# Sheet1.net
KiCad netlist of a schematic drawn in Altium Designer
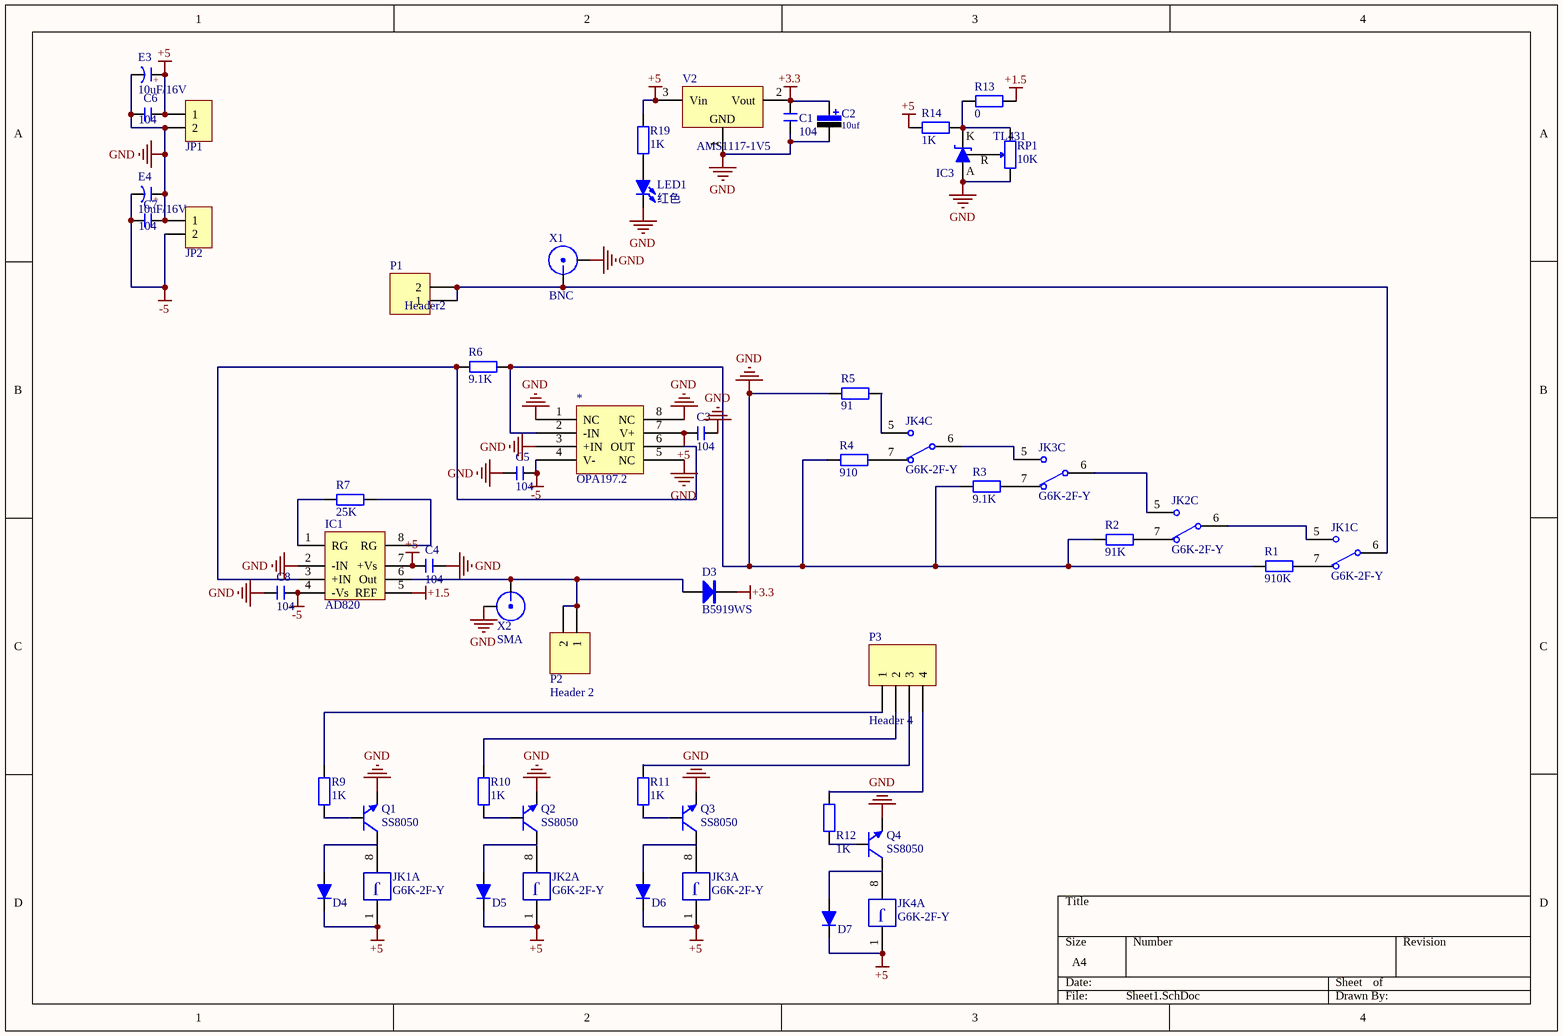
[diagram p0: Sheet1.SchDoc]

(export (version "E")
  (design (tool "Eeschema 10.0.6"))
  (components
    (comp (ref "*") (value "OPA197.2") (footprint "SOP-8") (libsource (lib "CommonUsed") (part "OPA197.2")))
    (comp (ref "C1")
      (value "104")
      (footprint "C 0603_L")
      (description "无极性贴片电容")
      (fields (field (name "版权归属") "源创客"))
      (libsource (lib "Library1") (part "C"))
    )
    (comp (ref "C2")
      (value "10uf")
      (footprint "C-DIP-5")
      (description "极性直插电解电容")
      (fields (field (name "Comment") "C"))
      (libsource (lib "Library") (part "Cap-Pol-ER"))
    )
    (comp (ref "C3")
      (value "104")
      (footprint "C 0603_L")
      (description "无极性贴片电容")
      (fields (field (name "版权归属") "源创客"))
      (libsource (lib "Library1") (part "C"))
    )
    (comp (ref "C4")
      (value "104")
      (footprint "C 0603_L")
      (description "无极性贴片电容")
      (fields (field (name "版权归属") "源创客"))
      (libsource (lib "Library1") (part "C"))
    )
    (comp (ref "C5")
      (value "104")
      (footprint "C 0603_L")
      (description "无极性贴片电容")
      (fields (field (name "版权归属") "源创客"))
      (libsource (lib "Library1") (part "C"))
    )
    (comp (ref "C6")
      (value "104")
      (footprint "C 0603_L")
      (description "无极性贴片电容")
      (fields (field (name "版权归属") "源创客"))
      (libsource (lib "Library1") (part "C"))
    )
    (comp (ref "C7")
      (value "104")
      (footprint "C 0603_L")
      (description "无极性贴片电容")
      (fields (field (name "版权归属") "源创客"))
      (libsource (lib "Library1") (part "C"))
    )
    (comp (ref "C8")
      (value "104")
      (footprint "C 0603_L")
      (description "无极性贴片电容")
      (fields (field (name "版权归属") "源创客"))
      (libsource (lib "Library1") (part "C"))
    )
    (comp (ref "D3")
      (value "B5919WS")
      (footprint "SMA")
      (description "肖特基二极管")
      (fields (field (name "版权归属") "源创客"))
      (libsource (lib "Library1") (part "1N5819"))
    )
    (comp (ref "D4")
      (value "D")
      (footprint "D-SMA")
      (description "二极管")
      (libsource (lib "Library") (part "Diode"))
    )
    (comp (ref "D5")
      (value "D")
      (footprint "D-SMA")
      (description "二极管")
      (libsource (lib "Library") (part "Diode"))
    )
    (comp (ref "D6")
      (value "D")
      (footprint "D-SMA")
      (description "二极管")
      (libsource (lib "Library") (part "Diode"))
    )
    (comp (ref "D7")
      (value "D")
      (footprint "D-SMA")
      (description "二极管")
      (libsource (lib "Library") (part "Diode"))
    )
    (comp (ref "E3")
      (value "10uF/16V")
      (footprint "CAP 2.5*5*11 - GD")
      (description "直插电解电容")
      (fields (field (name "版权归属") "源创客"))
      (libsource (lib "Library1") (part "C-CAP"))
    )
    (comp (ref "E4")
      (value "10uF/16V")
      (footprint "CAP 2.0*5*11")
      (description "直插电解电容")
      (fields (field (name "版权归属") "源创客"))
      (libsource (lib "Library1") (part "C-CAP"))
    )
    (comp (ref "IC1")
      (value "AD820")
      (footprint "SOP8_N")
      (description "仪表放大器")
      (libsource (lib "Library1") (part "AD620"))
    )
    (comp (ref "IC3")
      (value "TL431")
      (footprint "SOT23-3L")
      (description "可调基准稳压芯片")
      (fields (field (name "版权归属") "源创客"))
      (libsource (lib "Library1") (part "TL431_SMD"))
    )
    (comp (ref "JK1")
      (value "G6K-2F-Y")
      (footprint "G6K-2F-Y")
      (description "两组转换-信号型")
      (fields (field (name "版权归属") "源创客"))
      (libsource (lib "") (part "G6K-2F-Y_1"))
    )
    (comp (ref "JK2")
      (value "G6K-2F-Y")
      (footprint "G6K-2F-Y")
      (description "两组转换-信号型")
      (fields (field (name "版权归属") "源创客"))
      (libsource (lib "") (part "G6K-2F-Y_1"))
    )
    (comp (ref "JK3")
      (value "G6K-2F-Y")
      (footprint "G6K-2F-Y")
      (description "两组转换-信号型")
      (fields (field (name "版权归属") "源创客"))
      (libsource (lib "Library1") (part "G6K-2F-Y"))
    )
    (comp (ref "JK4")
      (value "G6K-2F-Y")
      (footprint "G6K-2F-Y")
      (description "两组转换-信号型")
      (fields (field (name "版权归属") "源创客"))
      (libsource (lib "") (part "G6K-2F-Y_1"))
    )
    (comp (ref "JP1")
      (value "HDR-1X2")
      (footprint "VH3.96-LI-2P")
      (description "2P接插件")
      (fields (field (name "版权归属") "源创客"))
      (libsource (lib "Library1") (part "Header 2"))
    )
    (comp (ref "JP2")
      (value "HDR-1X2")
      (footprint "VH3.96-LI-2P")
      (description "2P接插件")
      (fields (field (name "版权归属") "源创客"))
      (libsource (lib "Library1") (part "Header 2"))
    )
    (comp (ref "LED1")
      (value "红色")
      (footprint "LED 0805B")
      (description "贴片LED")
      (fields (field (name "版权归属") "源创客"))
      (libsource (lib "Library1") (part "LED-SMD"))
    )
    (comp (ref "P1")
      (value "Header2")
      (footprint "HDR1X2")
      (description "Header, 2-Pin")
      (fields (field (name "PUBLISHER") "Altium Limited"))
      (libsource (lib "") (part "Header 2_1"))
    )
    (comp (ref "P2")
      (value "Header 2")
      (footprint "HDR1X2")
      (description "Header, 2-Pin")
      (fields (field (name "PUBLISHER") "Altium Limited"))
      (libsource (lib "Miscellaneous Connectors") (part "Header 2"))
    )
    (comp (ref "P3")
      (value "Header 4")
      (footprint "HDR1X4")
      (description "Header, 4-Pin")
      (fields (field (name "PUBLISHER") "Altium Limited"))
      (libsource (lib "Miscellaneous Connectors") (part "Header 4"))
    )
    (comp (ref "Q1")
      (value "SS8050")
      (footprint "SOT23-3N")
      (description "高频放大-NPN型")
      (fields (field (name "版权归属") "源创客"))
      (libsource (lib "Library1") (part "8050-SMD"))
    )
    (comp (ref "Q2")
      (value "SS8050")
      (footprint "SOT23-3N")
      (description "高频放大-NPN型")
      (fields (field (name "版权归属") "源创客"))
      (libsource (lib "Library1") (part "8050-SMD"))
    )
    (comp (ref "Q3")
      (value "SS8050")
      (footprint "SOT23-3N")
      (description "高频放大-NPN型")
      (fields (field (name "版权归属") "源创客"))
      (libsource (lib "Library1") (part "8050-SMD"))
    )
    (comp (ref "Q4")
      (value "SS8050")
      (footprint "SOT23-3N")
      (description "高频放大-NPN型")
      (fields (field (name "版权归属") "源创客"))
      (libsource (lib "Library1") (part "8050-SMD"))
    )
    (comp (ref "R1")
      (value "910K")
      (footprint "R 0603_L")
      (description "贴片电阻")
      (fields (field (name "版权归属") "源创客"))
      (libsource (lib "Library1") (part "R"))
    )
    (comp (ref "R2")
      (value "91K")
      (footprint "R 0603_L")
      (description "贴片电阻")
      (fields (field (name "版权归属") "源创客"))
      (libsource (lib "Library1") (part "R"))
    )
    (comp (ref "R3")
      (value "9.1K")
      (footprint "R 0603_L")
      (description "贴片电阻")
      (fields (field (name "版权归属") "源创客"))
      (libsource (lib "Library1") (part "R"))
    )
    (comp (ref "R4")
      (value "910")
      (footprint "R 0603_L")
      (description "贴片电阻")
      (fields (field (name "版权归属") "源创客"))
      (libsource (lib "Library1") (part "R"))
    )
    (comp (ref "R5")
      (value "91")
      (footprint "R 0603_L")
      (description "贴片电阻")
      (fields (field (name "版权归属") "源创客"))
      (libsource (lib "Library1") (part "R"))
    )
    (comp (ref "R6")
      (value "9.1K")
      (footprint "R 0603_L")
      (description "贴片电阻")
      (fields (field (name "版权归属") "源创客"))
      (libsource (lib "Library1") (part "R"))
    )
    (comp (ref "R7")
      (value "25K")
      (footprint "R 0805_L")
      (description "贴片电阻")
      (fields (field (name "版权归属") "源创客"))
      (libsource (lib "Library1") (part "R"))
    )
    (comp (ref "R9")
      (value "1K")
      (footprint "R 0603_L")
      (description "贴片电阻")
      (fields (field (name "版权归属") "源创客"))
      (libsource (lib "Library1") (part "R"))
    )
    (comp (ref "R10")
      (value "1K")
      (footprint "R 0603_L")
      (description "贴片电阻")
      (fields (field (name "版权归属") "源创客"))
      (libsource (lib "Library1") (part "R"))
    )
    (comp (ref "R11")
      (value "1K")
      (footprint "R 0603_L")
      (description "贴片电阻")
      (fields (field (name "版权归属") "源创客"))
      (libsource (lib "Library1") (part "R"))
    )
    (comp (ref "R12")
      (value "1K")
      (footprint "R 0603_L")
      (description "贴片电阻")
      (fields (field (name "版权归属") "源创客"))
      (libsource (lib "Library1") (part "R"))
    )
    (comp (ref "R13")
      (value "0")
      (footprint "R 0603_L")
      (description "贴片电阻")
      (fields (field (name "版权归属") "源创客"))
      (libsource (lib "Library1") (part "R"))
    )
    (comp (ref "R14")
      (value "1K")
      (footprint "R 0603_L")
      (description "贴片电阻")
      (fields (field (name "版权归属") "源创客"))
      (libsource (lib "Library1") (part "R"))
    )
    (comp (ref "R19")
      (value "1K")
      (footprint "R 0603_L")
      (description "贴片电阻")
      (fields (field (name "版权归属") "源创客"))
      (libsource (lib "Library1") (part "R"))
    )
    (comp (ref "RP1")
      (value "10K")
      (footprint "3296W")
      (description "插件单联电位器")
      (fields (field (name "版权归属") "源创客"))
      (libsource (lib "Library1") (part "RP-ID"))
    )
    (comp (ref "V2")
      (value "AMS1117-1V5")
      (footprint "SOT223_L")
      (description "三端稳压芯片")
      (fields (field (name "版权归属") "源创客"))
      (libsource (lib "Library1") (part "AMS1117"))
    )
    (comp (ref "X1") (value "BNC") (footprint "BNC") (libsource (lib "Library") (part "BNC")))
    (comp (ref "X2") (value "SMA") (footprint "SMA1") (libsource (lib "Library") (part "SMA")))
  )
  (nets
    (net (code "1") (name "+1.5") (class "Default")
      (node (ref "IC1") (pin "5") (pinfunction "REF_5") (pintype "passive"))
      (node (ref "R13") (pin "1") (pinfunction "1_1") (pintype "passive"))
    )
    (net (code "2") (name "+3.3") (class "Default")
      (node (ref "C1") (pin "1") (pinfunction "1_1") (pintype "passive"))
      (node (ref "C2") (pin "1") (pinfunction "1_1") (pintype "passive"))
      (node (ref "D3") (pin "2") (pinfunction "K_2") (pintype "passive"))
      (node (ref "V2") (pin "2") (pinfunction "Vout_2") (pintype "passive"))
    )
    (net (code "3") (name "+5") (class "Default")
      (node (ref "*") (pin "7") (pinfunction "V+_7") (pintype "passive"))
      (node (ref "C3") (pin "2") (pinfunction "2_2") (pintype "passive"))
      (node (ref "C4") (pin "2") (pinfunction "2_2") (pintype "passive"))
      (node (ref "C6") (pin "2") (pinfunction "2_2") (pintype "passive"))
      (node (ref "D4") (pin "2") (pinfunction "2_2") (pintype "passive"))
      (node (ref "D5") (pin "2") (pinfunction "2_2") (pintype "passive"))
      (node (ref "D6") (pin "2") (pinfunction "2_2") (pintype "passive"))
      (node (ref "D7") (pin "2") (pinfunction "2_2") (pintype "passive"))
      (node (ref "E3") (pin "1") (pinfunction "A_1") (pintype "passive"))
      (node (ref "IC1") (pin "7") (pinfunction "+Vs_7") (pintype "passive"))
      (node (ref "JK1") (pin "1") (pinfunction "1_1") (pintype "passive"))
      (node (ref "JK2") (pin "1") (pinfunction "1_1") (pintype "passive"))
      (node (ref "JK3") (pin "1") (pinfunction "1_1") (pintype "passive"))
      (node (ref "JK4") (pin "1") (pinfunction "1_1") (pintype "passive"))
      (node (ref "JP1") (pin "1") (pinfunction "1_1") (pintype "passive"))
      (node (ref "R14") (pin "2") (pinfunction "2_2") (pintype "passive"))
      (node (ref "R19") (pin "1") (pinfunction "1_1") (pintype "passive"))
      (node (ref "V2") (pin "3") (pinfunction "Vin_3") (pintype "passive"))
    )
    (net (code "4") (name "-5") (class "Default")
      (node (ref "*") (pin "4") (pinfunction "V-_4") (pintype "passive"))
      (node (ref "C5") (pin "1") (pinfunction "1_1") (pintype "passive"))
      (node (ref "C7") (pin "1") (pinfunction "1_1") (pintype "passive"))
      (node (ref "C8") (pin "2") (pinfunction "2_2") (pintype "passive"))
      (node (ref "E4") (pin "2") (pinfunction "K_2") (pintype "passive"))
      (node (ref "IC1") (pin "4") (pinfunction "-Vs_4") (pintype "passive"))
      (node (ref "JP2") (pin "2") (pinfunction "2_2") (pintype "passive"))
    )
    (net (code "5") (name "GND") (class "Default")
      (node (ref "*") (pin "1") (pinfunction "NC_1") (pintype "passive"))
      (node (ref "*") (pin "2") (pinfunction "-IN_2") (pintype "passive"))
      (node (ref "*") (pin "3") (pinfunction "+IN_3") (pintype "passive"))
      (node (ref "*") (pin "5") (pinfunction "NC_5") (pintype "passive"))
      (node (ref "*") (pin "8") (pinfunction "NC_8") (pintype "passive"))
      (node (ref "C1") (pin "2") (pinfunction "2_2") (pintype "passive"))
      (node (ref "C2") (pin "2") (pinfunction "2_2") (pintype "passive"))
      (node (ref "C3") (pin "1") (pinfunction "1_1") (pintype "passive"))
      (node (ref "C4") (pin "1") (pinfunction "1_1") (pintype "passive"))
      (node (ref "C5") (pin "2") (pinfunction "2_2") (pintype "passive"))
      (node (ref "C6") (pin "1") (pinfunction "1_1") (pintype "passive"))
      (node (ref "C7") (pin "2") (pinfunction "2_2") (pintype "passive"))
      (node (ref "C8") (pin "1") (pinfunction "1_1") (pintype "passive"))
      (node (ref "E3") (pin "2") (pinfunction "K_2") (pintype "passive"))
      (node (ref "E4") (pin "1") (pinfunction "A_1") (pintype "passive"))
      (node (ref "IC1") (pin "2") (pinfunction "-IN_2") (pintype "passive"))
      (node (ref "IC3") (pin "3") (pinfunction "A_3") (pintype "passive"))
      (node (ref "JP1") (pin "2") (pinfunction "2_2") (pintype "passive"))
      (node (ref "JP2") (pin "1") (pinfunction "1_1") (pintype "passive"))
      (node (ref "LED1") (pin "2") (pinfunction "K_2") (pintype "passive"))
      (node (ref "Q1") (pin "2") (pinfunction "E_2") (pintype "passive"))
      (node (ref "Q2") (pin "2") (pinfunction "E_2") (pintype "passive"))
      (node (ref "Q3") (pin "2") (pinfunction "E_2") (pintype "passive"))
      (node (ref "Q4") (pin "2") (pinfunction "E_2") (pintype "passive"))
      (node (ref "R1") (pin "1") (pinfunction "1_1") (pintype "passive"))
      (node (ref "R2") (pin "1") (pinfunction "1_1") (pintype "passive"))
      (node (ref "R3") (pin "1") (pinfunction "1_1") (pintype "passive"))
      (node (ref "R4") (pin "1") (pinfunction "1_1") (pintype "passive"))
      (node (ref "R5") (pin "1") (pinfunction "1_1") (pintype "passive"))
      (node (ref "R6") (pin "2") (pinfunction "2_2") (pintype "passive"))
      (node (ref "RP1") (pin "1") (pinfunction "1_1") (pintype "passive"))
      (node (ref "V2") (pin "1") (pinfunction "GND_1") (pintype "passive"))
      (node (ref "X1") (pin "1") (pinfunction "1_1") (pintype "passive"))
      (node (ref "X2") (pin "2") (pinfunction "2_2") (pintype "passive"))
    )
    (net (code "6") (name "Net-(*-OUT)") (class "Default")
      (node (ref "*") (pin "6") (pinfunction "OUT_6") (pintype "passive"))
      (node (ref "IC1") (pin "3") (pinfunction "+IN_3") (pintype "passive"))
      (node (ref "R6") (pin "1") (pinfunction "1_1") (pintype "passive"))
    )
    (net (code "7") (name "Net-(D3-A)") (class "Default")
      (node (ref "D3") (pin "1") (pinfunction "A_1") (pintype "passive"))
      (node (ref "IC1") (pin "6") (pinfunction "Out_6") (pintype "passive"))
      (node (ref "P2") (pin "1") (pinfunction "1_1") (pintype "passive"))
      (node (ref "P2") (pin "2") (pinfunction "2_2") (pintype "passive"))
      (node (ref "X2") (pin "1") (pinfunction "1_1") (pintype "passive"))
    )
    (net (code "8") (name "Net-(IC1-RG-Pad1)") (class "Default")
      (node (ref "IC1") (pin "1") (pinfunction "RG_1") (pintype "passive"))
      (node (ref "R7") (pin "1") (pinfunction "1_1") (pintype "passive"))
    )
    (net (code "9") (name "Net-(IC1-RG-Pad8)") (class "Default")
      (node (ref "IC1") (pin "8") (pinfunction "RG_8") (pintype "passive"))
      (node (ref "R7") (pin "2") (pinfunction "2_2") (pintype "passive"))
    )
    (net (code "10") (name "Net-(IC3-K)") (class "Default")
      (node (ref "IC3") (pin "2") (pinfunction "K_2") (pintype "passive"))
      (node (ref "R13") (pin "2") (pinfunction "2_2") (pintype "passive"))
      (node (ref "R14") (pin "1") (pinfunction "1_1") (pintype "passive"))
      (node (ref "RP1") (pin "3") (pinfunction "3_3") (pintype "passive"))
    )
    (net (code "11") (name "Net-(IC3-R)") (class "Default")
      (node (ref "IC3") (pin "1") (pinfunction "R_1") (pintype "passive"))
      (node (ref "RP1") (pin "2") (pinfunction "2_2") (pintype "passive"))
    )
    (net (code "12") (name "Net-(JK1-Pad5)") (class "Default")
      (node (ref "JK1") (pin "5") (pinfunction "5_5") (pintype "passive"))
      (node (ref "JK2") (pin "6") (pinfunction "6_6") (pintype "passive"))
    )
    (net (code "13") (name "Net-(JK1-Pad6)") (class "Default")
      (node (ref "JK1") (pin "6") (pinfunction "6_6") (pintype "passive"))
      (node (ref "P1") (pin "1") (pinfunction "1_1") (pintype "passive"))
      (node (ref "P1") (pin "2") (pinfunction "2_2") (pintype "passive"))
      (node (ref "X1") (pin "2") (pinfunction "2_2") (pintype "passive"))
    )
    (net (code "14") (name "Net-(JK1-Pad7)") (class "Default")
      (node (ref "JK1") (pin "7") (pinfunction "7_7") (pintype "passive"))
      (node (ref "R1") (pin "2") (pinfunction "2_2") (pintype "passive"))
    )
    (net (code "15") (name "Net-(JK2-Pad5)") (class "Default")
      (node (ref "JK2") (pin "5") (pinfunction "5_5") (pintype "passive"))
      (node (ref "JK3") (pin "6") (pinfunction "6_6") (pintype "passive"))
    )
    (net (code "16") (name "Net-(JK2-Pad7)") (class "Default")
      (node (ref "JK2") (pin "7") (pinfunction "7_7") (pintype "passive"))
      (node (ref "R2") (pin "2") (pinfunction "2_2") (pintype "passive"))
    )
    (net (code "17") (name "Net-(JK3-Pad5)") (class "Default")
      (node (ref "JK3") (pin "5") (pinfunction "5_5") (pintype "passive"))
      (node (ref "JK4") (pin "6") (pinfunction "6_6") (pintype "passive"))
    )
    (net (code "18") (name "Net-(JK3-Pad7)") (class "Default")
      (node (ref "JK3") (pin "7") (pinfunction "7_7") (pintype "passive"))
      (node (ref "R3") (pin "2") (pinfunction "2_2") (pintype "passive"))
    )
    (net (code "19") (name "Net-(JK4-Pad5)") (class "Default")
      (node (ref "JK4") (pin "5") (pinfunction "5_5") (pintype "passive"))
      (node (ref "R5") (pin "2") (pinfunction "2_2") (pintype "passive"))
    )
    (net (code "20") (name "Net-(JK4-Pad7)") (class "Default")
      (node (ref "JK4") (pin "7") (pinfunction "7_7") (pintype "passive"))
      (node (ref "R4") (pin "2") (pinfunction "2_2") (pintype "passive"))
    )
    (net (code "21") (name "Net-(LED1-A)") (class "Default")
      (node (ref "LED1") (pin "1") (pinfunction "A_1") (pintype "passive"))
      (node (ref "R19") (pin "2") (pinfunction "2_2") (pintype "passive"))
    )
    (net (code "22") (name "Net-(P3-Pad1)") (class "Default")
      (node (ref "P3") (pin "1") (pinfunction "1_1") (pintype "passive"))
      (node (ref "R9") (pin "2") (pinfunction "2_2") (pintype "passive"))
    )
    (net (code "23") (name "Net-(P3-Pad2)") (class "Default")
      (node (ref "P3") (pin "2") (pinfunction "2_2") (pintype "passive"))
      (node (ref "R10") (pin "2") (pinfunction "2_2") (pintype "passive"))
    )
    (net (code "24") (name "Net-(P3-Pad3)") (class "Default")
      (node (ref "P3") (pin "3") (pinfunction "3_3") (pintype "passive"))
      (node (ref "R11") (pin "2") (pinfunction "2_2") (pintype "passive"))
    )
    (net (code "25") (name "Net-(P3-Pad4)") (class "Default")
      (node (ref "P3") (pin "4") (pinfunction "4_4") (pintype "passive"))
      (node (ref "R12") (pin "2") (pinfunction "2_2") (pintype "passive"))
    )
    (net (code "26") (name "Net-(Q1-B)") (class "Default")
      (node (ref "Q1") (pin "1") (pinfunction "B_1") (pintype "passive"))
      (node (ref "R9") (pin "1") (pinfunction "1_1") (pintype "passive"))
    )
    (net (code "27") (name "Net-(Q1-C)") (class "Default")
      (node (ref "D4") (pin "1") (pinfunction "1_1") (pintype "passive"))
      (node (ref "Q1") (pin "3") (pinfunction "C_3") (pintype "passive"))
    )
    (net (code "28") (name "Net-(Q2-B)") (class "Default")
      (node (ref "Q2") (pin "1") (pinfunction "B_1") (pintype "passive"))
      (node (ref "R10") (pin "1") (pinfunction "1_1") (pintype "passive"))
    )
    (net (code "29") (name "Net-(Q2-C)") (class "Default")
      (node (ref "D5") (pin "1") (pinfunction "1_1") (pintype "passive"))
      (node (ref "Q2") (pin "3") (pinfunction "C_3") (pintype "passive"))
    )
    (net (code "30") (name "Net-(Q3-B)") (class "Default")
      (node (ref "Q3") (pin "1") (pinfunction "B_1") (pintype "passive"))
      (node (ref "R11") (pin "1") (pinfunction "1_1") (pintype "passive"))
    )
    (net (code "31") (name "Net-(Q3-C)") (class "Default")
      (node (ref "D6") (pin "1") (pinfunction "1_1") (pintype "passive"))
      (node (ref "Q3") (pin "3") (pinfunction "C_3") (pintype "passive"))
    )
    (net (code "32") (name "Net-(Q4-B)") (class "Default")
      (node (ref "Q4") (pin "1") (pinfunction "B_1") (pintype "passive"))
      (node (ref "R12") (pin "1") (pinfunction "1_1") (pintype "passive"))
    )
    (net (code "33") (name "Net-(Q4-C)") (class "Default")
      (node (ref "D7") (pin "1") (pinfunction "1_1") (pintype "passive"))
      (node (ref "Q4") (pin "3") (pinfunction "C_3") (pintype "passive"))
    )
    (net (code "34") (name "unconnected-(JK1-Pad8)") (class "Default")
      (node (ref "JK1") (pin "8") (pinfunction "8_8") (pintype "passive"))
    )
    (net (code "35") (name "unconnected-(JK2-Pad8)") (class "Default")
      (node (ref "JK2") (pin "8") (pinfunction "8_8") (pintype "passive"))
    )
    (net (code "36") (name "unconnected-(JK3-Pad8)") (class "Default")
      (node (ref "JK3") (pin "8") (pinfunction "8_8") (pintype "passive"))
    )
    (net (code "37") (name "unconnected-(JK4-Pad8)") (class "Default")
      (node (ref "JK4") (pin "8") (pinfunction "8_8") (pintype "passive"))
    )
  )
)
